# powerctl.net
KiCad netlist of a schematic drawn in EAGLE
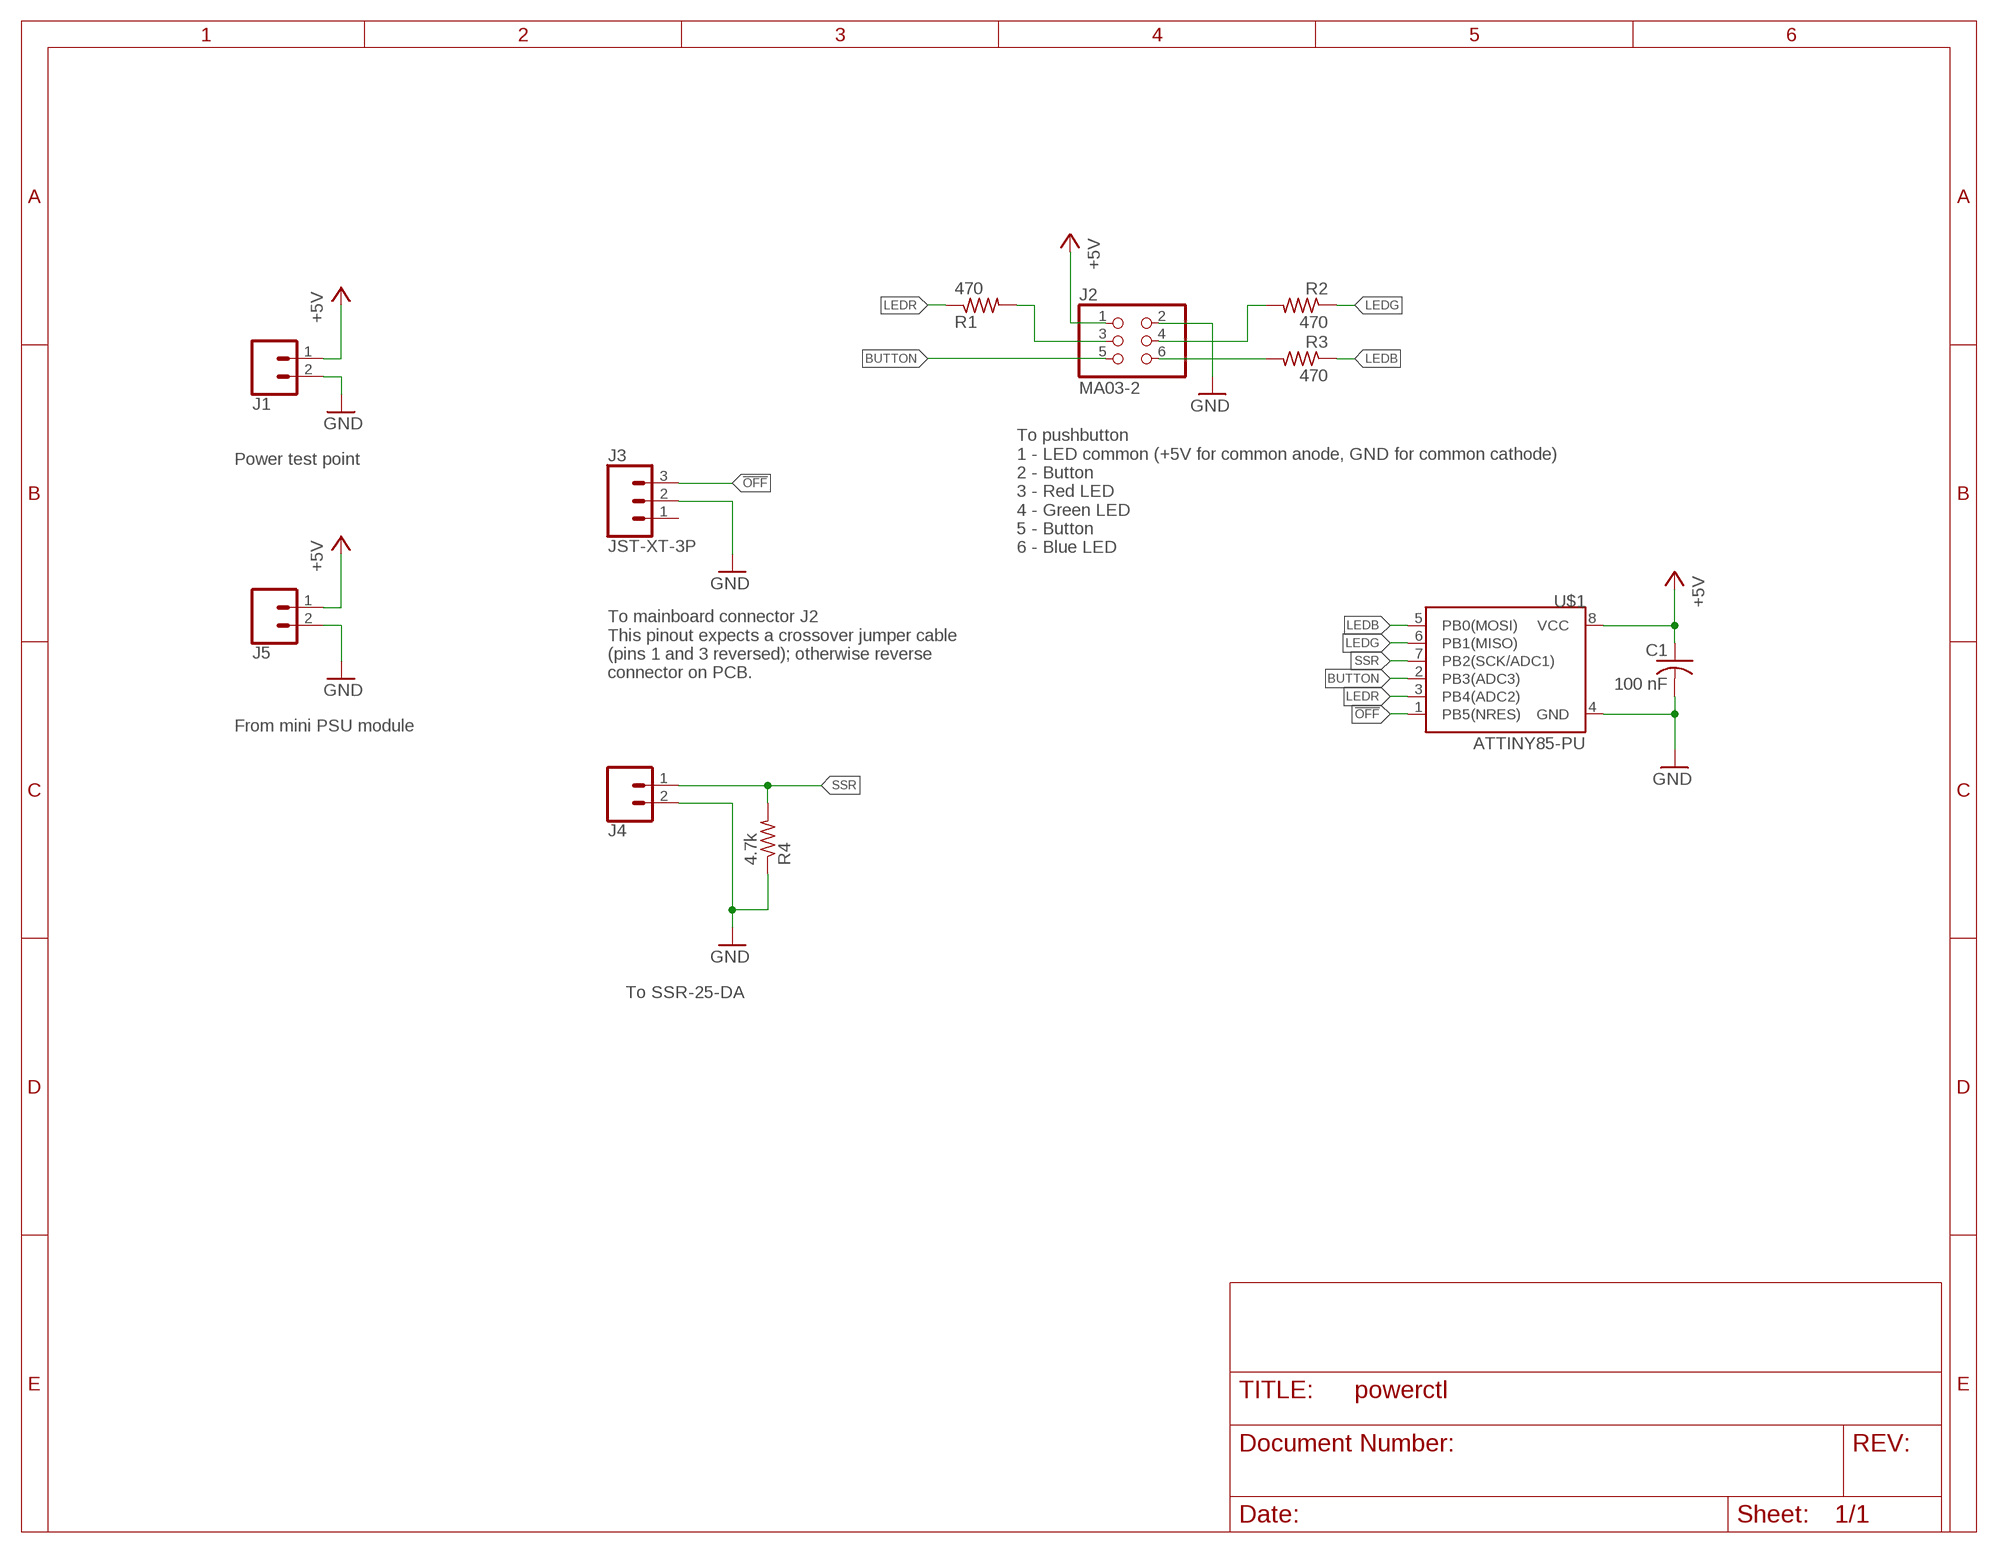
[diagram p0: schematic, sheet 1]

(export (version "E")
  (design (tool "Eeschema 10.0.6"))
  (components
    (comp (ref "C1")
      (value "100 nF")
      (footprint "eagle-import:C025-025X050")
      (libsource (lib "eagle-import") (part "C-US025-025X050"))
    )
    (comp (ref "J1")
      (value "CONN_02")
      (footprint "eagle-import:1X02")
      (libsource (lib "eagle-import") (part "CONN_02"))
    )
    (comp (ref "J2")
      (value "MA03-2")
      (footprint "eagle-import:2X03")
      (libsource (lib "eagle-import") (part "PINHD-2X3"))
    )
    (comp (ref "J3")
      (value "JST-XT-3P")
      (footprint "eagle-import:1X03")
      (libsource (lib "eagle-import") (part "CONN_03"))
    )
    (comp (ref "J4")
      (value "CONN_02")
      (footprint "eagle-import:1X02")
      (libsource (lib "eagle-import") (part "CONN_02"))
    )
    (comp (ref "J5")
      (value "CONN_02")
      (footprint "eagle-import:1X02")
      (libsource (lib "eagle-import") (part "CONN_02"))
    )
    (comp (ref "R1")
      (value "470")
      (footprint "eagle-import:0207_15")
      (libsource (lib "eagle-import") (part "R-US_0207/15"))
    )
    (comp (ref "R2")
      (value "470")
      (footprint "eagle-import:0207_15")
      (libsource (lib "eagle-import") (part "R-US_0207/15"))
    )
    (comp (ref "R3")
      (value "470")
      (footprint "eagle-import:0207_15")
      (libsource (lib "eagle-import") (part "R-US_0207/15"))
    )
    (comp (ref "R4")
      (value "4.7k")
      (footprint "eagle-import:0207_15")
      (libsource (lib "eagle-import") (part "R-US_0207/15"))
    )
    (comp (ref "U$1")
      (value "ATTINY85-PU")
      (footprint "eagle-import:DIP08")
      (libsource (lib "eagle-import") (part "ATTINY13DIP"))
    )
  )
  (nets
    (net (code "1") (name "+5V") (class "Default")
      (node (ref "C1") (pin "1") (pinfunction "1_1") (pintype "passive"))
      (node (ref "J1") (pin "1") (pinfunction "1_1") (pintype "passive"))
      (node (ref "J2") (pin "1") (pinfunction "1_1") (pintype "passive"))
      (node (ref "J5") (pin "1") (pinfunction "1_1") (pintype "passive"))
      (node (ref "U$1") (pin "8") (pinfunction "VCC_8") (pintype "bidirectional"))
    )
    (net (code "2") (name "/~{OFF}") (class "Default")
      (node (ref "J3") (pin "3") (pinfunction "3_3") (pintype "passive"))
      (node (ref "U$1") (pin "1") (pinfunction "PB5(NRES)_1") (pintype "bidirectional"))
    )
    (net (code "3") (name "BUTTON") (class "Default")
      (node (ref "J2") (pin "5") (pinfunction "5_5") (pintype "passive"))
      (node (ref "U$1") (pin "2") (pinfunction "PB3(ADC3)_2") (pintype "bidirectional"))
    )
    (net (code "4") (name "GND") (class "Default")
      (node (ref "C1") (pin "2") (pinfunction "2_2") (pintype "passive"))
      (node (ref "J1") (pin "2") (pinfunction "2_2") (pintype "passive"))
      (node (ref "J2") (pin "2") (pinfunction "2_2") (pintype "passive"))
      (node (ref "J3") (pin "2") (pinfunction "2_2") (pintype "passive"))
      (node (ref "J4") (pin "2") (pinfunction "2_2") (pintype "passive"))
      (node (ref "J5") (pin "2") (pinfunction "2_2") (pintype "passive"))
      (node (ref "R4") (pin "1") (pinfunction "1_1") (pintype "passive"))
      (node (ref "U$1") (pin "4") (pinfunction "GND_4") (pintype "bidirectional"))
    )
    (net (code "5") (name "LEDB") (class "Default")
      (node (ref "R3") (pin "1") (pinfunction "1_1") (pintype "passive"))
      (node (ref "U$1") (pin "5") (pinfunction "PB0(MOSI)_5") (pintype "bidirectional"))
    )
    (net (code "6") (name "LEDG") (class "Default")
      (node (ref "R2") (pin "1") (pinfunction "1_1") (pintype "passive"))
      (node (ref "U$1") (pin "6") (pinfunction "PB1(MISO)_6") (pintype "bidirectional"))
    )
    (net (code "7") (name "LEDR") (class "Default")
      (node (ref "R1") (pin "1") (pinfunction "1_1") (pintype "passive"))
      (node (ref "U$1") (pin "3") (pinfunction "PB4(ADC2)_3") (pintype "bidirectional"))
    )
    (net (code "8") (name "Net-(J2-Pad3)") (class "Default")
      (node (ref "J2") (pin "3") (pinfunction "3_3") (pintype "passive"))
      (node (ref "R1") (pin "2") (pinfunction "2_2") (pintype "passive"))
    )
    (net (code "9") (name "Net-(J2-Pad4)") (class "Default")
      (node (ref "J2") (pin "4") (pinfunction "4_4") (pintype "passive"))
      (node (ref "R2") (pin "2") (pinfunction "2_2") (pintype "passive"))
    )
    (net (code "10") (name "Net-(J2-Pad6)") (class "Default")
      (node (ref "J2") (pin "6") (pinfunction "6_6") (pintype "passive"))
      (node (ref "R3") (pin "2") (pinfunction "2_2") (pintype "passive"))
    )
    (net (code "11") (name "SSR") (class "Default")
      (node (ref "J4") (pin "1") (pinfunction "1_1") (pintype "passive"))
      (node (ref "R4") (pin "2") (pinfunction "2_2") (pintype "passive"))
      (node (ref "U$1") (pin "7") (pinfunction "PB2(SCK/ADC1)_7") (pintype "bidirectional"))
    )
    (net (code "12") (name "unconnected-(J3-Pad1)") (class "Default")
      (node (ref "J3") (pin "1") (pinfunction "1_1") (pintype "passive"))
    )
  )
)
